# gear.net
KiCad netlist of a schematic drawn in EAGLE
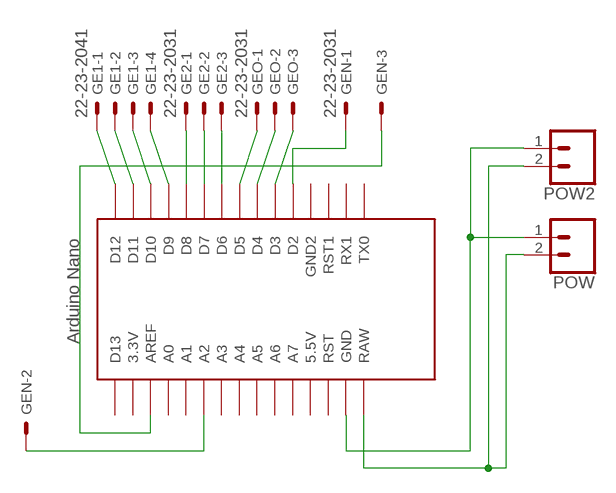
[diagram p0: schematic, sheet 1]

(export (version "E")
  (design (tool "Eeschema 10.0.6"))
  (components
    (comp (ref "GE1")
      (value "22-23-2041")
      (footprint "eagle-import:22-23-2041")
      (fields (field (name "MF") "MOLEX"))
      (libsource (lib "eagle-import") (part "22-23-2041"))
    )
    (comp (ref "GE2")
      (value "22-23-2031")
      (footprint "eagle-import:22-23-2031")
      (fields (field (name "MF") "MOLEX"))
      (libsource (lib "eagle-import") (part "22-23-2031"))
    )
    (comp (ref "GEN")
      (value "22-23-2031")
      (footprint "eagle-import:22-23-2031")
      (fields (field (name "MF") "MOLEX"))
      (libsource (lib "eagle-import") (part "22-23-2031"))
    )
    (comp (ref "GEO")
      (value "22-23-2031")
      (footprint "eagle-import:22-23-2031")
      (fields (field (name "MF") "MOLEX"))
      (libsource (lib "eagle-import") (part "22-23-2031"))
    )
    (comp (ref "POW")
      (value "CONN_025MM")
      (footprint "eagle-import:SCREWTERMINAL-5MM-2")
      (libsource (lib "eagle-import") (part "CONN_025MM"))
    )
    (comp (ref "POW2")
      (value "CONN_025MM")
      (footprint "eagle-import:SCREWTERMINAL-5MM-2")
      (libsource (lib "eagle-import") (part "CONN_025MM"))
    )
    (comp (ref "U$1")
      (value "NANO")
      (footprint "eagle-import:NANO")
      (libsource (lib "eagle-import") (part "NANO"))
    )
  )
  (nets
    (net (code "1") (name "Net-(GE1A-S)") (class "Default")
      (node (ref "GE1") (pin "1") (pinfunction "S_1") (pintype "passive"))
      (node (ref "U$1") (pin "D12") (pinfunction "D12_D12") (pintype "bidirectional"))
    )
    (net (code "2") (name "Net-(GE1B-S)") (class "Default")
      (node (ref "GE1") (pin "2") (pinfunction "S_2") (pintype "passive"))
      (node (ref "U$1") (pin "D11") (pinfunction "D11_D11") (pintype "bidirectional"))
    )
    (net (code "3") (name "Net-(GE1C-S)") (class "Default")
      (node (ref "GE1") (pin "3") (pinfunction "S_3") (pintype "passive"))
      (node (ref "U$1") (pin "D10") (pinfunction "D10_D10") (pintype "bidirectional"))
    )
    (net (code "4") (name "Net-(GE1D-S)") (class "Default")
      (node (ref "GE1") (pin "4") (pinfunction "S_4") (pintype "passive"))
      (node (ref "U$1") (pin "D9") (pinfunction "D9_D9") (pintype "bidirectional"))
    )
    (net (code "5") (name "Net-(GE2A-S)") (class "Default")
      (node (ref "GE2") (pin "1") (pinfunction "S_1") (pintype "passive"))
      (node (ref "U$1") (pin "D8") (pinfunction "D8_D8") (pintype "bidirectional"))
    )
    (net (code "6") (name "Net-(GE2B-S)") (class "Default")
      (node (ref "GE2") (pin "2") (pinfunction "S_2") (pintype "passive"))
      (node (ref "U$1") (pin "D7") (pinfunction "D7_D7") (pintype "bidirectional"))
    )
    (net (code "7") (name "Net-(GE2C-S)") (class "Default")
      (node (ref "GE2") (pin "3") (pinfunction "S_3") (pintype "passive"))
      (node (ref "U$1") (pin "D6") (pinfunction "D6_D6") (pintype "bidirectional"))
    )
    (net (code "8") (name "Net-(GENA-S)") (class "Default")
      (node (ref "GEN") (pin "1") (pinfunction "S_1") (pintype "passive"))
      (node (ref "U$1") (pin "D2") (pinfunction "D2_D2") (pintype "bidirectional"))
    )
    (net (code "9") (name "Net-(GENB-S)") (class "Default")
      (node (ref "GEN") (pin "2") (pinfunction "S_2") (pintype "passive"))
      (node (ref "U$1") (pin "A2") (pinfunction "A2_A2") (pintype "bidirectional"))
    )
    (net (code "10") (name "Net-(GENC-S)") (class "Default")
      (node (ref "GEN") (pin "3") (pinfunction "S_3") (pintype "passive"))
      (node (ref "U$1") (pin "AREF") (pinfunction "AREF_AREF") (pintype "bidirectional"))
    )
    (net (code "11") (name "Net-(GEOA-S)") (class "Default")
      (node (ref "GEO") (pin "1") (pinfunction "S_1") (pintype "passive"))
      (node (ref "U$1") (pin "D5") (pinfunction "D5_D5") (pintype "bidirectional"))
    )
    (net (code "12") (name "Net-(GEOB-S)") (class "Default")
      (node (ref "GEO") (pin "2") (pinfunction "S_2") (pintype "passive"))
      (node (ref "U$1") (pin "D4") (pinfunction "D4_D4") (pintype "bidirectional"))
    )
    (net (code "13") (name "Net-(GEOC-S)") (class "Default")
      (node (ref "GEO") (pin "3") (pinfunction "S_3") (pintype "passive"))
      (node (ref "U$1") (pin "D3") (pinfunction "D3_D3") (pintype "bidirectional"))
    )
    (net (code "14") (name "Net-(POW-Pad1)") (class "Default")
      (node (ref "POW") (pin "1") (pinfunction "1_1") (pintype "passive"))
      (node (ref "POW2") (pin "1") (pinfunction "1_1") (pintype "passive"))
      (node (ref "U$1") (pin "GND") (pinfunction "GND_GND") (pintype "bidirectional"))
    )
    (net (code "15") (name "Net-(POW-Pad2)") (class "Default")
      (node (ref "POW") (pin "2") (pinfunction "2_2") (pintype "passive"))
      (node (ref "POW2") (pin "2") (pinfunction "2_2") (pintype "passive"))
      (node (ref "U$1") (pin "RAW") (pinfunction "RAW_RAW") (pintype "bidirectional"))
    )
    (net (code "16") (name "unconnected-(U$1-5.5V-Pad5V)") (class "Default")
      (node (ref "U$1") (pin "5V") (pinfunction "5.5V_5V") (pintype "bidirectional"))
    )
    (net (code "17") (name "unconnected-(U$1-GND2-PadGND1)") (class "Default")
      (node (ref "U$1") (pin "GND1") (pinfunction "GND2_GND1") (pintype "bidirectional"))
    )
    (net (code "18") (name "unconnected-(U$1-Pad3.3V)") (class "Default")
      (node (ref "U$1") (pin "3.3V") (pinfunction "3.3V_3.3V") (pintype "bidirectional"))
    )
    (net (code "19") (name "unconnected-(U$1-PadA0)") (class "Default")
      (node (ref "U$1") (pin "A0") (pinfunction "A0_A0") (pintype "bidirectional"))
    )
    (net (code "20") (name "unconnected-(U$1-PadA1)") (class "Default")
      (node (ref "U$1") (pin "A1") (pinfunction "A1_A1") (pintype "bidirectional"))
    )
    (net (code "21") (name "unconnected-(U$1-PadA3)") (class "Default")
      (node (ref "U$1") (pin "A3") (pinfunction "A3_A3") (pintype "bidirectional"))
    )
    (net (code "22") (name "unconnected-(U$1-PadA4)") (class "Default")
      (node (ref "U$1") (pin "A4") (pinfunction "A4_A4") (pintype "bidirectional"))
    )
    (net (code "23") (name "unconnected-(U$1-PadA5)") (class "Default")
      (node (ref "U$1") (pin "A5") (pinfunction "A5_A5") (pintype "bidirectional"))
    )
    (net (code "24") (name "unconnected-(U$1-PadA6)") (class "Default")
      (node (ref "U$1") (pin "A6") (pinfunction "A6_A6") (pintype "bidirectional"))
    )
    (net (code "25") (name "unconnected-(U$1-PadA7)") (class "Default")
      (node (ref "U$1") (pin "A7") (pinfunction "A7_A7") (pintype "bidirectional"))
    )
    (net (code "26") (name "unconnected-(U$1-PadD13)") (class "Default")
      (node (ref "U$1") (pin "D13") (pinfunction "D13_D13") (pintype "bidirectional"))
    )
    (net (code "27") (name "unconnected-(U$1-PadICSP1)") (class "Default")
      (node (ref "U$1") (pin "ICSP1") (pinfunction "ICSP1_ICSP1") (pintype "bidirectional"))
    )
    (net (code "28") (name "unconnected-(U$1-PadICSP2)") (class "Default")
      (node (ref "U$1") (pin "ICSP2") (pinfunction "ICSP2_ICSP2") (pintype "bidirectional"))
    )
    (net (code "29") (name "unconnected-(U$1-PadICSP3)") (class "Default")
      (node (ref "U$1") (pin "ICSP3") (pinfunction "ICSP3_ICSP3") (pintype "bidirectional"))
    )
    (net (code "30") (name "unconnected-(U$1-PadICSP4)") (class "Default")
      (node (ref "U$1") (pin "ICSP4") (pinfunction "ICSP4_ICSP4") (pintype "bidirectional"))
    )
    (net (code "31") (name "unconnected-(U$1-PadICSP5)") (class "Default")
      (node (ref "U$1") (pin "ICSP5") (pinfunction "ICSP5_ICSP5") (pintype "bidirectional"))
    )
    (net (code "32") (name "unconnected-(U$1-PadICSP6)") (class "Default")
      (node (ref "U$1") (pin "ICSP6") (pinfunction "ICSP6_ICSP6") (pintype "bidirectional"))
    )
    (net (code "33") (name "unconnected-(U$1-PadRST)") (class "Default")
      (node (ref "U$1") (pin "RST") (pinfunction "RST_RST") (pintype "bidirectional"))
    )
    (net (code "34") (name "unconnected-(U$1-PadRST1)") (class "Default")
      (node (ref "U$1") (pin "RST1") (pinfunction "RST1_RST1") (pintype "bidirectional"))
    )
    (net (code "35") (name "unconnected-(U$1-PadRX1)") (class "Default")
      (node (ref "U$1") (pin "RX1") (pinfunction "RX1_RX1") (pintype "bidirectional"))
    )
    (net (code "36") (name "unconnected-(U$1-PadTX0)") (class "Default")
      (node (ref "U$1") (pin "TX0") (pinfunction "TX0_TX0") (pintype "bidirectional"))
    )
  )
)
